# Differential_Channel_Protection.net
KiCad netlist of a schematic drawn in Altium Designer
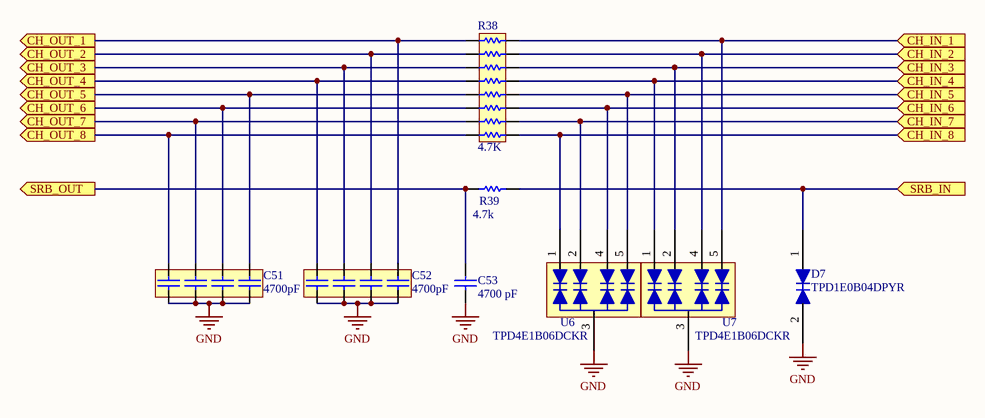
[diagram p0: Differential Channel Protection.SchDoc]

(export (version "E")
  (design (tool "Eeschema 10.0.6"))
  (components
    (comp (ref "C51")
      (value "50V")
      (footprint "1206C-ARRAY")
      (description "CAP .1UF 50V CERAMIC Y5V 0805")
      (fields
        (field (name "MANUFACTURER") "TDK")
        (field (name "PCN PART NUMBER") "MLCC Part Number Change 30/Nov/2012")
        (field (name "CAPACITANCE") "4700pF")
      )
      (libsource (lib "LUCHADOR SCHLIB") (part "Cap"))
    )
    (comp (ref "C52")
      (value "50V")
      (footprint "1206C-ARRAY")
      (description "CAP .1UF 50V CERAMIC Y5V 0805")
      (fields
        (field (name "MANUFACTURER") "TDK")
        (field (name "PCN PART NUMBER") "MLCC Part Number Change 30/Nov/2012")
        (field (name "CAPACITANCE") "4700pF")
      )
      (libsource (lib "LUCHADOR SCHLIB") (part "Cap"))
    )
    (comp (ref "C53")
      (value "50V")
      (footprint "0402C")
      (description "CAP .1UF 50V CERAMIC Y5V 0805")
      (fields
        (field (name "MANUFACTURER") "Murata")
        (field (name "MANUFACTURER PART NUMBER") "GCM155R71H472KA37D")
        (field (name "CAPACITANCE") "4700 pF")
      )
      (libsource (lib "Miscellaneous Devices") (part "Cap"))
    )
    (comp (ref "D7")
      (value "TPD1E0B04DPYR")
      (footprint "0402D")
      (fields
        (field (name "MANUFACTURER") "Texas Instruments")
        (field (name "MANUFACTURER PART NUMBER") "TPD1E0B04DPYR")
      )
      (libsource (lib "LUCHADOR SCHLIB") (part "TPD1E0B04DPYR"))
    )
    (comp (ref "R38")
      (value "RES 8X")
      (footprint "1506R")
      (description "Resistor")
      (fields
        (field (name "MANUFACTURER") "Panasonic")
        (field (name "MANUFACTURER PART NUMBER") "EXB-2HV472JV")
        (field (name "RESISTANCE") "4.7K")
      )
      (libsource (lib "LUCHADOR SCHLIB") (part "RES 8X"))
    )
    (comp (ref "R39")
      (value "Res 0805")
      (footprint "0402R")
      (description "Resistor")
      (fields
        (field (name "MANUFACTURER") "Samsung")
        (field (name "MANUFACTURER PART NUMBER") "RC1005F472CS")
        (field (name "RESISTANCE VALUE") "4.7k")
      )
      (libsource (lib "RAPTOR MCB SCHLIB") (part "Res 0805"))
    )
    (comp (ref "U6")
      (value "TPD4E1B06DCKR")
      (footprint "SC70-6")
      (fields
        (field (name "MANUFACTURER") "Texas Instruments")
        (field (name "MANUFACTURER PART NUMBER") "TPD4E1B06DCKR")
      )
      (libsource (lib "LUCHADOR SCHLIB") (part "TPD4E1B06DCKR"))
    )
    (comp (ref "U7")
      (value "TPD4E1B06DCKR")
      (footprint "SC70-6")
      (fields
        (field (name "MANUFACTURER") "Texas Instruments")
        (field (name "MANUFACTURER PART NUMBER") "TPD4E1B06DCKR")
      )
      (libsource (lib "LUCHADOR SCHLIB") (part "TPD4E1B06DCKR"))
    )
  )
  (nets
    (net (code "1") (name "/CH_IN_1") (class "Default")
      (node (ref "R38") (pin "B1") (pinfunction "B1_B1") (pintype "passive"))
      (node (ref "U7") (pin "5") (pinfunction "IO4_5") (pintype "passive"))
    )
    (net (code "2") (name "/CH_IN_2") (class "Default")
      (node (ref "R38") (pin "B2") (pinfunction "B2_B2") (pintype "passive"))
      (node (ref "U7") (pin "4") (pinfunction "IO3_4") (pintype "passive"))
    )
    (net (code "3") (name "/CH_IN_3") (class "Default")
      (node (ref "R38") (pin "B3") (pinfunction "B3_B3") (pintype "passive"))
      (node (ref "U7") (pin "2") (pinfunction "IO2_2") (pintype "passive"))
    )
    (net (code "4") (name "/CH_IN_4") (class "Default")
      (node (ref "R38") (pin "B4") (pinfunction "B4_B4") (pintype "passive"))
      (node (ref "U7") (pin "1") (pinfunction "IO1_1") (pintype "passive"))
    )
    (net (code "5") (name "/CH_IN_5") (class "Default")
      (node (ref "R38") (pin "B5") (pinfunction "B5_B5") (pintype "passive"))
      (node (ref "U6") (pin "5") (pinfunction "IO4_5") (pintype "passive"))
    )
    (net (code "6") (name "/CH_IN_6") (class "Default")
      (node (ref "R38") (pin "B6") (pinfunction "B6_B6") (pintype "passive"))
      (node (ref "U6") (pin "4") (pinfunction "IO3_4") (pintype "passive"))
    )
    (net (code "7") (name "/CH_IN_7") (class "Default")
      (node (ref "R38") (pin "B7") (pinfunction "B7_B7") (pintype "passive"))
      (node (ref "U6") (pin "2") (pinfunction "IO2_2") (pintype "passive"))
    )
    (net (code "8") (name "/CH_IN_8") (class "Default")
      (node (ref "R38") (pin "B8") (pinfunction "B8_B8") (pintype "passive"))
      (node (ref "U6") (pin "1") (pinfunction "IO1_1") (pintype "passive"))
    )
    (net (code "9") (name "/CH_OUT_1") (class "Default")
      (node (ref "C52") (pin "A1") (pinfunction "A1_A1") (pintype "passive"))
      (node (ref "R38") (pin "A1") (pinfunction "A1_A1") (pintype "passive"))
    )
    (net (code "10") (name "/CH_OUT_2") (class "Default")
      (node (ref "C52") (pin "A2") (pinfunction "A2_A2") (pintype "passive"))
      (node (ref "R38") (pin "A2") (pinfunction "A2_A2") (pintype "passive"))
    )
    (net (code "11") (name "/CH_OUT_3") (class "Default")
      (node (ref "C52") (pin "A3") (pinfunction "A3_A3") (pintype "passive"))
      (node (ref "R38") (pin "A3") (pinfunction "A3_A3") (pintype "passive"))
    )
    (net (code "12") (name "/CH_OUT_4") (class "Default")
      (node (ref "C52") (pin "A4") (pinfunction "A4_A4") (pintype "passive"))
      (node (ref "R38") (pin "A4") (pinfunction "A4_A4") (pintype "passive"))
    )
    (net (code "13") (name "/CH_OUT_5") (class "Default")
      (node (ref "C51") (pin "A1") (pinfunction "A1_A1") (pintype "passive"))
      (node (ref "R38") (pin "A5") (pinfunction "A5_A5") (pintype "passive"))
    )
    (net (code "14") (name "/CH_OUT_6") (class "Default")
      (node (ref "C51") (pin "A2") (pinfunction "A2_A2") (pintype "passive"))
      (node (ref "R38") (pin "A6") (pinfunction "A6_A6") (pintype "passive"))
    )
    (net (code "15") (name "/CH_OUT_7") (class "Default")
      (node (ref "C51") (pin "A3") (pinfunction "A3_A3") (pintype "passive"))
      (node (ref "R38") (pin "A7") (pinfunction "A7_A7") (pintype "passive"))
    )
    (net (code "16") (name "/CH_OUT_8") (class "Default")
      (node (ref "C51") (pin "A4") (pinfunction "A4_A4") (pintype "passive"))
      (node (ref "R38") (pin "A8") (pinfunction "A8_A8") (pintype "passive"))
    )
    (net (code "17") (name "/SRB_IN") (class "Default")
      (node (ref "D7") (pin "1") (pinfunction "IO1_1") (pintype "passive"))
      (node (ref "R39") (pin "2") (pinfunction "2_2") (pintype "passive"))
    )
    (net (code "18") (name "/SRB_OUT") (class "Default")
      (node (ref "C53") (pin "2") (pinfunction "2_2") (pintype "passive"))
      (node (ref "R39") (pin "1") (pinfunction "1_1") (pintype "passive"))
    )
    (net (code "19") (name "GND") (class "Default")
      (node (ref "C51") (pin "B1") (pinfunction "B1_B1") (pintype "passive"))
      (node (ref "C51") (pin "B2") (pinfunction "B2_B2") (pintype "passive"))
      (node (ref "C51") (pin "B3") (pinfunction "B3_B3") (pintype "passive"))
      (node (ref "C51") (pin "B4") (pinfunction "B4_B4") (pintype "passive"))
      (node (ref "C52") (pin "B1") (pinfunction "B1_B1") (pintype "passive"))
      (node (ref "C52") (pin "B2") (pinfunction "B2_B2") (pintype "passive"))
      (node (ref "C52") (pin "B3") (pinfunction "B3_B3") (pintype "passive"))
      (node (ref "C52") (pin "B4") (pinfunction "B4_B4") (pintype "passive"))
      (node (ref "C53") (pin "1") (pinfunction "1_1") (pintype "passive"))
      (node (ref "D7") (pin "2") (pinfunction "GND_2") (pintype "passive"))
      (node (ref "U6") (pin "3") (pinfunction "GND_3") (pintype "passive"))
      (node (ref "U7") (pin "3") (pinfunction "GND_3") (pintype "passive"))
    )
  )
)
